# rooftop_reflector.net
KiCad netlist of a schematic drawn in EAGLE
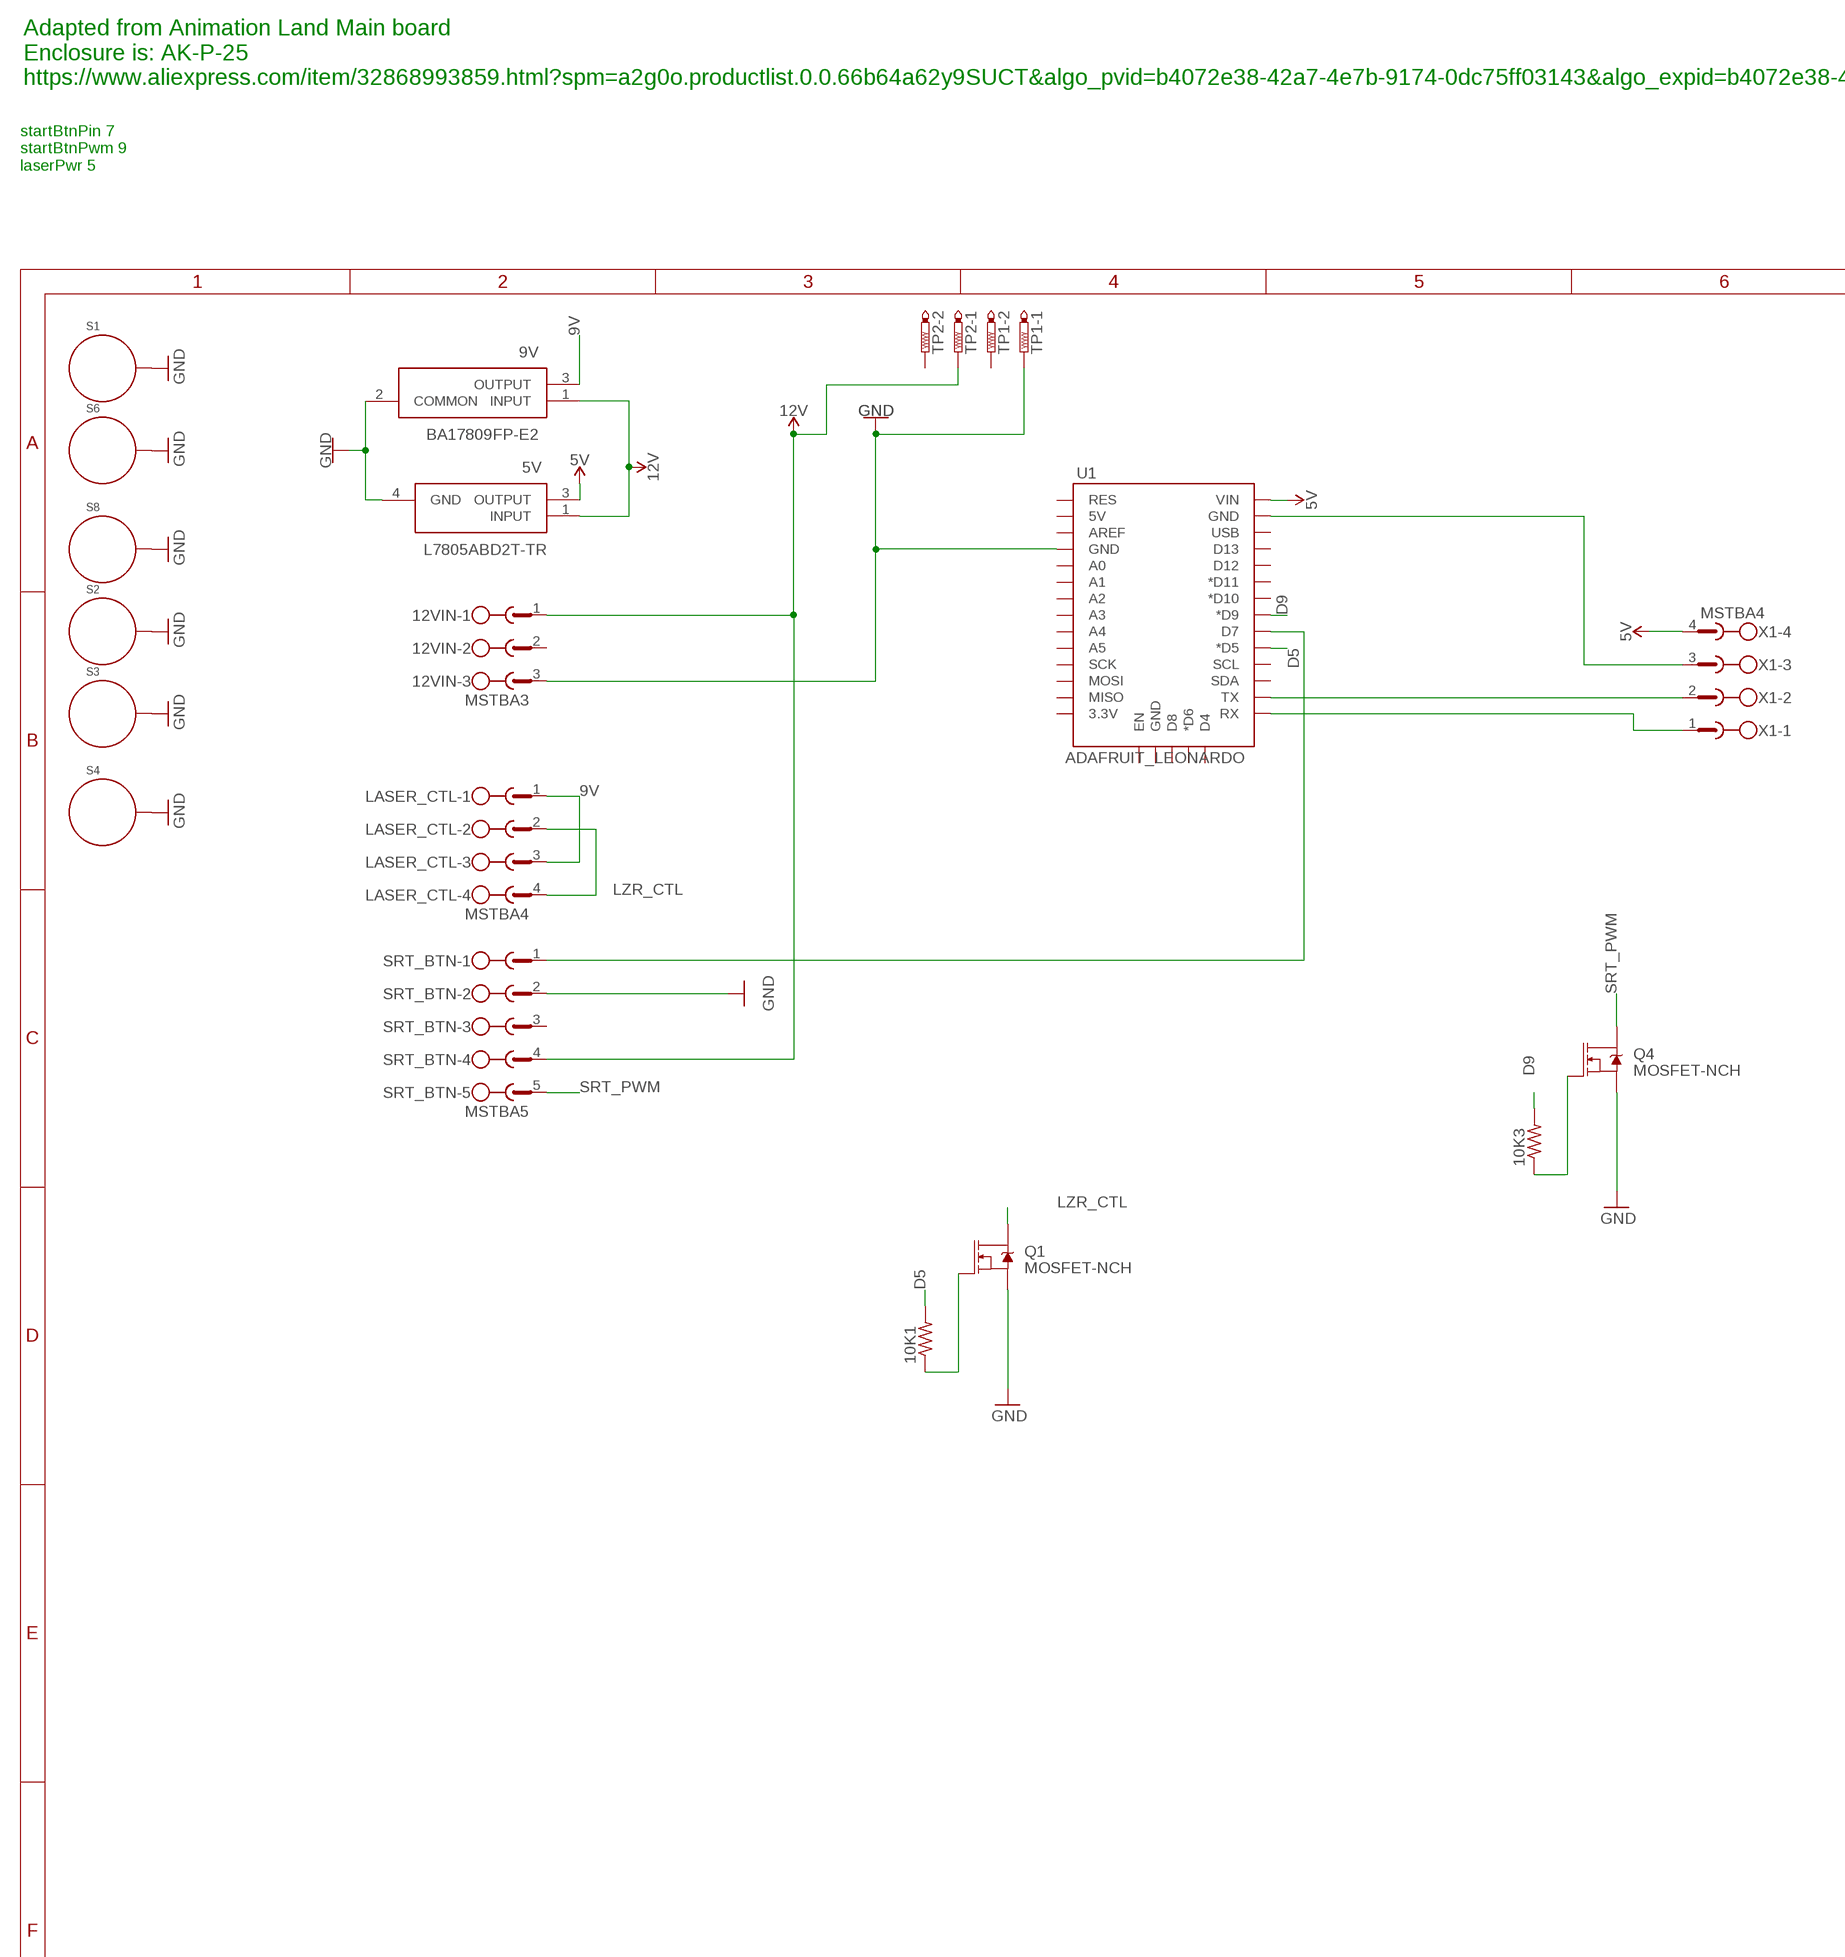
[diagram p0: schematic, sheet 1, part 1 of 2]
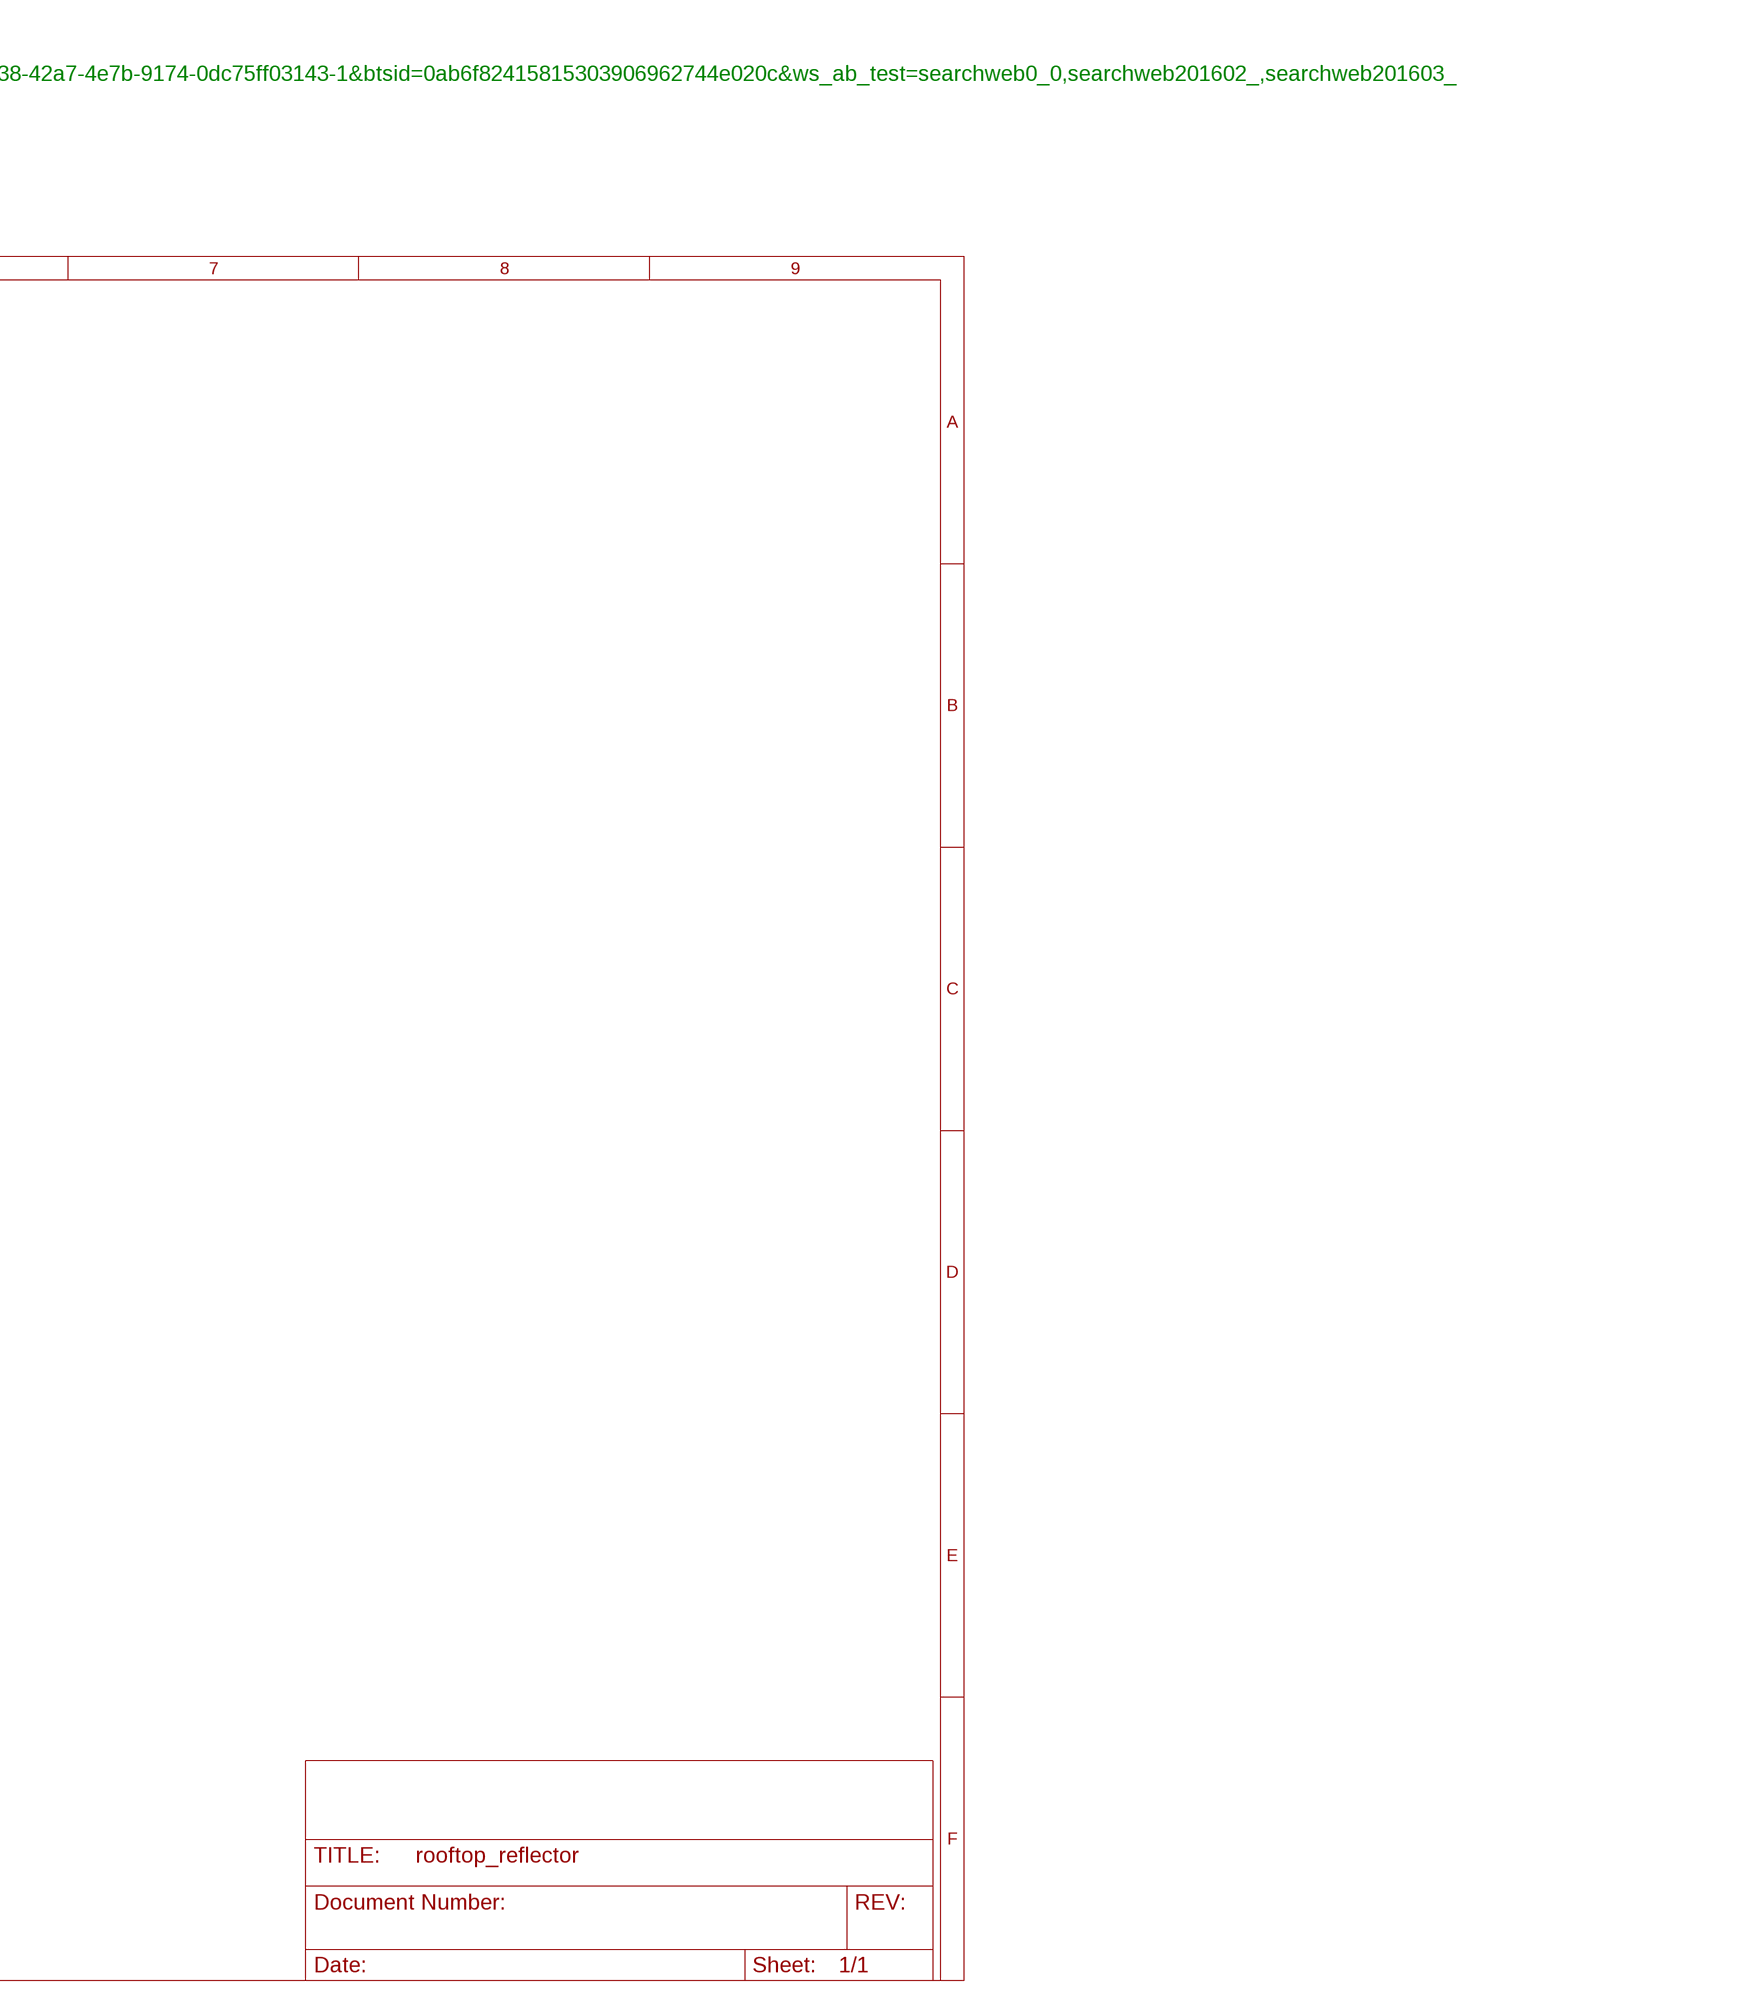
[diagram p1: schematic, sheet 1, part 2 of 2]

(export (version "E")
  (design (tool "Eeschema 10.0.6"))
  (components
    (comp (ref "5V")
      (value "L7805ABD2T-TR")
      (footprint "eagle-import:D2PAK-STB35NF10T4")
      (fields (field (name "MOUSER_PART_NUMBER") "511-L7805ABD2T-TR"))
      (libsource (lib "eagle-import") (part "L7805ABD2T-TR"))
    )
    (comp (ref "9V")
      (value "BA17809FP-E2")
      (footprint "eagle-import:BA17809FPE2")
      (fields (field (name "MOUSER_PART_NUMBER") "755-BA17809FP-E2"))
      (libsource (lib "eagle-import") (part "BA17809FP-E2"))
    )
    (comp (ref "10K1")
      (value "R-US_M0805")
      (footprint "eagle-import:M0805")
      (libsource (lib "eagle-import") (part "R-US_M0805"))
    )
    (comp (ref "10K3")
      (value "R-US_M0805")
      (footprint "eagle-import:M0805")
      (libsource (lib "eagle-import") (part "R-US_M0805"))
    )
    (comp (ref "12VIN")
      (value "MSTBA3")
      (footprint "eagle-import:MSTBA3")
      (fields (field (name "MF") "FARNELL") (field (name "MPN") "1757255"))
      (libsource (lib "eagle-import") (part "MSTBA3"))
    )
    (comp (ref "LASER_CTL")
      (value "MSTBA4")
      (footprint "eagle-import:MSTBA4")
      (fields (field (name "MF") "FARNELL") (field (name "MPN") "1757268"))
      (libsource (lib "eagle-import") (part "MSTBA4"))
    )
    (comp (ref "Q1")
      (value "MOSFET-NCH")
      (footprint "eagle-import:SO-8_POWER_PAK")
      (libsource (lib "eagle-import") (part "MOSFET-NCH"))
    )
    (comp (ref "Q4")
      (value "MOSFET-NCH")
      (footprint "eagle-import:SO-8_POWER_PAK")
      (libsource (lib "eagle-import") (part "MOSFET-NCH"))
    )
    (comp (ref "S1")
      (value "STANDOFF_ELECTRICAL5-32")
      (footprint "eagle-import:STANDOFF_ELECTRICAL_5_32")
      (libsource (lib "eagle-import") (part "STANDOFF_ELECTRICAL5-32"))
    )
    (comp (ref "S2")
      (value "STANDOFF_ELECTRICAL5-32")
      (footprint "eagle-import:STANDOFF_ELECTRICAL_5_32")
      (libsource (lib "eagle-import") (part "STANDOFF_ELECTRICAL5-32"))
    )
    (comp (ref "S3")
      (value "STANDOFF_ELECTRICAL5-32")
      (footprint "eagle-import:STANDOFF_ELECTRICAL_5_32")
      (libsource (lib "eagle-import") (part "STANDOFF_ELECTRICAL5-32"))
    )
    (comp (ref "S4")
      (value "STANDOFF_ELECTRICAL5-32")
      (footprint "eagle-import:STANDOFF_ELECTRICAL_5_32")
      (libsource (lib "eagle-import") (part "STANDOFF_ELECTRICAL5-32"))
    )
    (comp (ref "S6")
      (value "STANDOFF_ELECTRICAL5-32")
      (footprint "eagle-import:STANDOFF_ELECTRICAL_5_32")
      (libsource (lib "eagle-import") (part "STANDOFF_ELECTRICAL5-32"))
    )
    (comp (ref "S8")
      (value "STANDOFF_ELECTRICAL5-32")
      (footprint "eagle-import:STANDOFF_ELECTRICAL_5_32")
      (libsource (lib "eagle-import") (part "STANDOFF_ELECTRICAL5-32"))
    )
    (comp (ref "SRT_BTN")
      (value "MSTBA5")
      (footprint "eagle-import:MSTBA5")
      (fields (field (name "MPN") "1757271"))
      (libsource (lib "eagle-import") (part "MSTBA5"))
    )
    (comp (ref "TP1")
      (value "PTR2")
      (footprint "eagle-import:P2-38-17")
      (libsource (lib "eagle-import") (part "PTR2"))
    )
    (comp (ref "TP2")
      (value "PTR2")
      (footprint "eagle-import:P2-38-17")
      (libsource (lib "eagle-import") (part "PTR2"))
    )
    (comp (ref "U1")
      (value "ADAFRUIT_LEONARDO")
      (footprint "eagle-import:ADAFRUIT_LENOARDO")
      (libsource (lib "eagle-import") (part "ADAFRUIT_LEONARDO"))
    )
    (comp (ref "X1")
      (value "MSTBA4")
      (footprint "eagle-import:MSTBA4")
      (fields (field (name "MF") "FARNELL") (field (name "MPN") "1757268"))
      (libsource (lib "eagle-import") (part "MSTBA4"))
    )
  )
  (nets
    (net (code "1") (name "/9V") (class "Default")
      (node (ref "9V") (pin "3") (pinfunction "OUTPUT_3") (pintype "bidirectional"))
      (node (ref "LASER_CTL") (pin "1") (pinfunction "1_1") (pintype "passive"))
      (node (ref "LASER_CTL") (pin "3") (pinfunction "1_3") (pintype "passive"))
    )
    (net (code "2") (name "/D5") (class "Default")
      (node (ref "10K1") (pin "2") (pinfunction "2_2") (pintype "passive"))
      (node (ref "U1") (pin "D5") (pinfunction "*D5_D5") (pintype "bidirectional"))
    )
    (net (code "3") (name "/D9") (class "Default")
      (node (ref "10K3") (pin "2") (pinfunction "2_2") (pintype "passive"))
      (node (ref "U1") (pin "D9") (pinfunction "*D9_D9") (pintype "bidirectional"))
    )
    (net (code "4") (name "/LZR_CTL") (class "Default")
      (node (ref "LASER_CTL") (pin "2") (pinfunction "1_2") (pintype "passive"))
      (node (ref "LASER_CTL") (pin "4") (pinfunction "1_4") (pintype "passive"))
      (node (ref "Q1") (pin "D1") (pinfunction "D_D1") (pintype "bidirectional"))
    )
    (net (code "5") (name "/SRT_PWM") (class "Default")
      (node (ref "Q4") (pin "D1") (pinfunction "D_D1") (pintype "bidirectional"))
      (node (ref "SRT_BTN") (pin "5") (pinfunction "1_5") (pintype "passive"))
    )
    (net (code "6") (name "5V") (class "Default")
      (node (ref "5V") (pin "3") (pinfunction "OUTPUT_3") (pintype "bidirectional"))
      (node (ref "U1") (pin "VIN") (pinfunction "VIN_VIN") (pintype "bidirectional"))
      (node (ref "X1") (pin "4") (pinfunction "1_4") (pintype "passive"))
    )
    (net (code "7") (name "12V") (class "Default")
      (node (ref "12VIN") (pin "1") (pinfunction "1_1") (pintype "passive"))
      (node (ref "5V") (pin "1") (pinfunction "INPUT_1") (pintype "bidirectional"))
      (node (ref "9V") (pin "1") (pinfunction "INPUT_1") (pintype "bidirectional"))
      (node (ref "SRT_BTN") (pin "4") (pinfunction "1_4") (pintype "passive"))
      (node (ref "TP2") (pin "TP-1") (pinfunction "TP_TP-1") (pintype "input"))
    )
    (net (code "8") (name "GND") (class "Default")
      (node (ref "12VIN") (pin "3") (pinfunction "1_3") (pintype "passive"))
      (node (ref "5V") (pin "4") (pinfunction "GND_4") (pintype "bidirectional"))
      (node (ref "9V") (pin "2") (pinfunction "COMMON_2") (pintype "bidirectional"))
      (node (ref "Q1") (pin "S") (pinfunction "S_S") (pintype "bidirectional"))
      (node (ref "Q4") (pin "S") (pinfunction "S_S") (pintype "bidirectional"))
      (node (ref "S1") (pin "P1") (pinfunction "P$1_P1") (pintype "bidirectional"))
      (node (ref "S2") (pin "P1") (pinfunction "P$1_P1") (pintype "bidirectional"))
      (node (ref "S3") (pin "P1") (pinfunction "P$1_P1") (pintype "bidirectional"))
      (node (ref "S4") (pin "P1") (pinfunction "P$1_P1") (pintype "bidirectional"))
      (node (ref "S6") (pin "P1") (pinfunction "P$1_P1") (pintype "bidirectional"))
      (node (ref "S8") (pin "P1") (pinfunction "P$1_P1") (pintype "bidirectional"))
      (node (ref "SRT_BTN") (pin "2") (pinfunction "1_2") (pintype "passive"))
      (node (ref "TP1") (pin "TP-1") (pinfunction "TP_TP-1") (pintype "input"))
      (node (ref "U1") (pin "GND@0") (pinfunction "GND_GND@0") (pintype "bidirectional"))
    )
    (net (code "9") (name "Net-(10K1-Pad1)") (class "Default")
      (node (ref "10K1") (pin "1") (pinfunction "1_1") (pintype "passive"))
      (node (ref "Q1") (pin "G") (pinfunction "G_G") (pintype "bidirectional"))
    )
    (net (code "10") (name "Net-(10K3-Pad1)") (class "Default")
      (node (ref "10K3") (pin "1") (pinfunction "1_1") (pintype "passive"))
      (node (ref "Q4") (pin "G") (pinfunction "G_G") (pintype "bidirectional"))
    )
    (net (code "11") (name "Net-(SRT_BTN-Pad1)") (class "Default")
      (node (ref "SRT_BTN") (pin "1") (pinfunction "1_1") (pintype "passive"))
      (node (ref "U1") (pin "D7") (pinfunction "D7_D7") (pintype "bidirectional"))
    )
    (net (code "12") (name "Net-(U1-PadRX)") (class "Default")
      (node (ref "U1") (pin "RX") (pinfunction "RX_RX") (pintype "bidirectional"))
      (node (ref "X1") (pin "1") (pinfunction "1_1") (pintype "passive"))
    )
    (net (code "13") (name "Net-(X1B-1)") (class "Default")
      (node (ref "U1") (pin "TX") (pinfunction "TX_TX") (pintype "bidirectional"))
      (node (ref "X1") (pin "2") (pinfunction "1_2") (pintype "passive"))
    )
    (net (code "14") (name "Net-(X1C-1)") (class "Default")
      (node (ref "U1") (pin "GND@2") (pinfunction "GND_GND@2") (pintype "bidirectional"))
      (node (ref "X1") (pin "3") (pinfunction "1_3") (pintype "passive"))
    )
    (net (code "15") (name "unconnected-(12VINB-1-Pad2)") (class "Default")
      (node (ref "12VIN") (pin "2") (pinfunction "1_2") (pintype "passive"))
    )
    (net (code "16") (name "unconnected-(SRT_BTNC-1-Pad3)") (class "Default")
      (node (ref "SRT_BTN") (pin "3") (pinfunction "1_3") (pintype "passive"))
    )
    (net (code "17") (name "unconnected-(TP1B-TP-PadTP-2)") (class "Default")
      (node (ref "TP1") (pin "TP-2") (pinfunction "TP_TP-2") (pintype "input"))
    )
    (net (code "18") (name "unconnected-(TP2B-TP-PadTP-2)") (class "Default")
      (node (ref "TP2") (pin "TP-2") (pinfunction "TP_TP-2") (pintype "input"))
    )
    (net (code "19") (name "unconnected-(U1-*D6-PadD6)") (class "Default")
      (node (ref "U1") (pin "D6") (pinfunction "*D6_D6") (pintype "bidirectional"))
    )
    (net (code "20") (name "unconnected-(U1-*D10-PadD10)") (class "Default")
      (node (ref "U1") (pin "D10") (pinfunction "*D10_D10") (pintype "bidirectional"))
    )
    (net (code "21") (name "unconnected-(U1-*D11-PadD11)") (class "Default")
      (node (ref "U1") (pin "D11") (pinfunction "*D11_D11") (pintype "bidirectional"))
    )
    (net (code "22") (name "unconnected-(U1-3.3V-Pad3V)") (class "Default")
      (node (ref "U1") (pin "3V") (pinfunction "3.3V_3V") (pintype "bidirectional"))
    )
    (net (code "23") (name "unconnected-(U1-GND-PadGND@1)") (class "Default")
      (node (ref "U1") (pin "GND@1") (pinfunction "GND_GND@1") (pintype "bidirectional"))
    )
    (net (code "24") (name "unconnected-(U1-Pad5V)") (class "Default")
      (node (ref "U1") (pin "5V") (pinfunction "5V_5V") (pintype "bidirectional"))
    )
    (net (code "25") (name "unconnected-(U1-PadA0)") (class "Default")
      (node (ref "U1") (pin "A0") (pinfunction "A0_A0") (pintype "bidirectional"))
    )
    (net (code "26") (name "unconnected-(U1-PadA1)") (class "Default")
      (node (ref "U1") (pin "A1") (pinfunction "A1_A1") (pintype "bidirectional"))
    )
    (net (code "27") (name "unconnected-(U1-PadA2)") (class "Default")
      (node (ref "U1") (pin "A2") (pinfunction "A2_A2") (pintype "bidirectional"))
    )
    (net (code "28") (name "unconnected-(U1-PadA3)") (class "Default")
      (node (ref "U1") (pin "A3") (pinfunction "A3_A3") (pintype "bidirectional"))
    )
    (net (code "29") (name "unconnected-(U1-PadA4)") (class "Default")
      (node (ref "U1") (pin "A4") (pinfunction "A4_A4") (pintype "bidirectional"))
    )
    (net (code "30") (name "unconnected-(U1-PadA5)") (class "Default")
      (node (ref "U1") (pin "A5") (pinfunction "A5_A5") (pintype "bidirectional"))
    )
    (net (code "31") (name "unconnected-(U1-PadAREF)") (class "Default")
      (node (ref "U1") (pin "AREF") (pinfunction "AREF_AREF") (pintype "bidirectional"))
    )
    (net (code "32") (name "unconnected-(U1-PadD4)") (class "Default")
      (node (ref "U1") (pin "D4") (pinfunction "D4_D4") (pintype "bidirectional"))
    )
    (net (code "33") (name "unconnected-(U1-PadD8)") (class "Default")
      (node (ref "U1") (pin "D8") (pinfunction "D8_D8") (pintype "bidirectional"))
    )
    (net (code "34") (name "unconnected-(U1-PadD12)") (class "Default")
      (node (ref "U1") (pin "D12") (pinfunction "D12_D12") (pintype "bidirectional"))
    )
    (net (code "35") (name "unconnected-(U1-PadD13)") (class "Default")
      (node (ref "U1") (pin "D13") (pinfunction "D13_D13") (pintype "bidirectional"))
    )
    (net (code "36") (name "unconnected-(U1-PadEN)") (class "Default")
      (node (ref "U1") (pin "EN") (pinfunction "EN_EN") (pintype "bidirectional"))
    )
    (net (code "37") (name "unconnected-(U1-PadMISO)") (class "Default")
      (node (ref "U1") (pin "MISO") (pinfunction "MISO_MISO") (pintype "bidirectional"))
    )
    (net (code "38") (name "unconnected-(U1-PadMOSI)") (class "Default")
      (node (ref "U1") (pin "MOSI") (pinfunction "MOSI_MOSI") (pintype "bidirectional"))
    )
    (net (code "39") (name "unconnected-(U1-PadRES)") (class "Default")
      (node (ref "U1") (pin "RES") (pinfunction "RES_RES") (pintype "bidirectional"))
    )
    (net (code "40") (name "unconnected-(U1-PadSCK)") (class "Default")
      (node (ref "U1") (pin "SCK") (pinfunction "SCK_SCK") (pintype "bidirectional"))
    )
    (net (code "41") (name "unconnected-(U1-PadSCL)") (class "Default")
      (node (ref "U1") (pin "SCL") (pinfunction "SCL_SCL") (pintype "bidirectional"))
    )
    (net (code "42") (name "unconnected-(U1-PadSDA)") (class "Default")
      (node (ref "U1") (pin "SDA") (pinfunction "SDA_SDA") (pintype "bidirectional"))
    )
    (net (code "43") (name "unconnected-(U1-PadUSB)") (class "Default")
      (node (ref "U1") (pin "USB") (pinfunction "USB_USB") (pintype "bidirectional"))
    )
  )
)
